# modbus.net
KiCad netlist of a schematic drawn in EAGLE
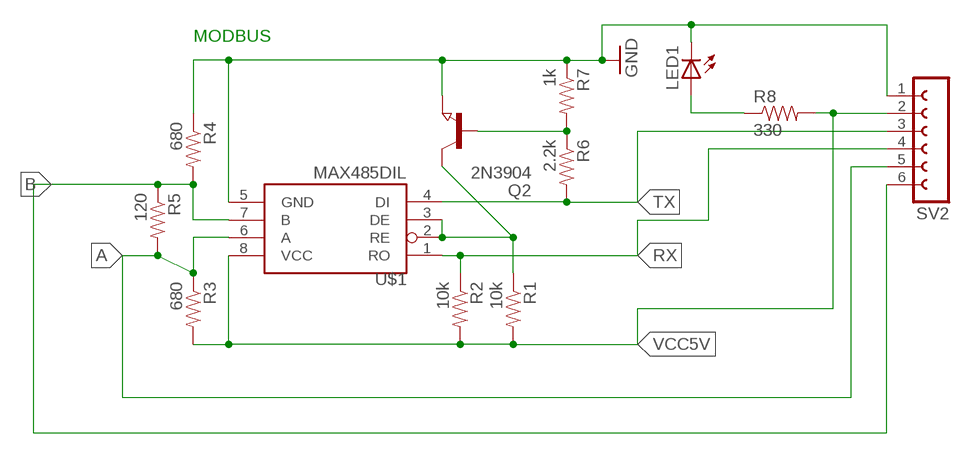
[diagram p0: schematic, sheet 1]

(export (version "E")
  (design (tool "Eeschema 10.0.6"))
  (components
    (comp (ref "LED1")
      (value "LEDCHIP-LED0805")
      (footprint "eagle-import:CHIP-LED0805")
      (libsource (lib "eagle-import") (part "LEDCHIP-LED0805"))
    )
    (comp (ref "Q2")
      (value "2N3904")
      (footprint "eagle-import:SOT23")
      (libsource (lib "eagle-import") (part "NPN-TRANSISTOR_SOT23"))
    )
    (comp (ref "R1")
      (value "10k")
      (footprint "eagle-import:0805")
      (libsource (lib "eagle-import") (part "RESISTOR0805-RES"))
    )
    (comp (ref "R2")
      (value "10k")
      (footprint "eagle-import:0805")
      (libsource (lib "eagle-import") (part "RESISTOR0805-RES"))
    )
    (comp (ref "R3")
      (value "680")
      (footprint "eagle-import:0805")
      (libsource (lib "eagle-import") (part "RESISTOR0805-RES"))
    )
    (comp (ref "R4")
      (value "680")
      (footprint "eagle-import:0805")
      (libsource (lib "eagle-import") (part "RESISTOR0805-RES"))
    )
    (comp (ref "R5")
      (value "120")
      (footprint "eagle-import:0805")
      (libsource (lib "eagle-import") (part "RESISTOR0805-RES"))
    )
    (comp (ref "R6")
      (value "2.2k")
      (footprint "eagle-import:0805")
      (libsource (lib "eagle-import") (part "RESISTOR0805-RES"))
    )
    (comp (ref "R7")
      (value "1k")
      (footprint "eagle-import:0805")
      (libsource (lib "eagle-import") (part "RESISTOR0805-RES"))
    )
    (comp (ref "R8")
      (value "330")
      (footprint "eagle-import:0805")
      (libsource (lib "eagle-import") (part "RESISTOR0805-RES"))
    )
    (comp (ref "SV2")
      (value "FE06-1")
      (footprint "eagle-import:FE06")
      (libsource (lib "eagle-import") (part "FE06-1"))
    )
    (comp (ref "U$1")
      (value "MAX485DIL")
      (footprint "eagle-import:DIL08")
      (libsource (lib "eagle-import") (part "MAX485DIL"))
    )
  )
  (nets
    (net (code "1") (name "A") (class "Default")
      (node (ref "R3") (pin "1") (pinfunction "1_1") (pintype "passive"))
      (node (ref "R5") (pin "2") (pinfunction "2_2") (pintype "passive"))
      (node (ref "SV2") (pin "5") (pinfunction "5_5") (pintype "passive"))
      (node (ref "U$1") (pin "6") (pinfunction "A_6") (pintype "bidirectional"))
    )
    (net (code "2") (name "B") (class "Default")
      (node (ref "R4") (pin "2") (pinfunction "2_2") (pintype "passive"))
      (node (ref "R5") (pin "1") (pinfunction "1_1") (pintype "passive"))
      (node (ref "SV2") (pin "6") (pinfunction "6_6") (pintype "passive"))
      (node (ref "U$1") (pin "7") (pinfunction "B_7") (pintype "bidirectional"))
    )
    (net (code "3") (name "GND") (class "Default")
      (node (ref "LED1") (pin "C") (pinfunction "C_C") (pintype "passive"))
      (node (ref "Q2") (pin "2") (pinfunction "E_2") (pintype "passive"))
      (node (ref "R4") (pin "1") (pinfunction "1_1") (pintype "passive"))
      (node (ref "R7") (pin "1") (pinfunction "1_1") (pintype "passive"))
      (node (ref "SV2") (pin "1") (pinfunction "1_1") (pintype "passive"))
      (node (ref "U$1") (pin "5") (pinfunction "GND_5") (pintype "bidirectional"))
    )
    (net (code "4") (name "Net-(LED1-PadA)") (class "Default")
      (node (ref "LED1") (pin "A") (pinfunction "A_A") (pintype "passive"))
      (node (ref "R8") (pin "1") (pinfunction "1_1") (pintype "passive"))
    )
    (net (code "5") (name "Net-(Q2-B)") (class "Default")
      (node (ref "Q2") (pin "1") (pinfunction "B_1") (pintype "passive"))
      (node (ref "R6") (pin "1") (pinfunction "1_1") (pintype "passive"))
      (node (ref "R7") (pin "2") (pinfunction "2_2") (pintype "passive"))
    )
    (net (code "6") (name "Net-(Q2-C)") (class "Default")
      (node (ref "Q2") (pin "3") (pinfunction "C_3") (pintype "passive"))
      (node (ref "R1") (pin "1") (pinfunction "1_1") (pintype "passive"))
      (node (ref "U$1") (pin "2") (pinfunction "RE_2") (pintype "bidirectional"))
      (node (ref "U$1") (pin "3") (pinfunction "DE_3") (pintype "bidirectional"))
    )
    (net (code "7") (name "RX") (class "Default")
      (node (ref "R2") (pin "1") (pinfunction "1_1") (pintype "passive"))
      (node (ref "SV2") (pin "4") (pinfunction "4_4") (pintype "passive"))
      (node (ref "U$1") (pin "1") (pinfunction "RO_1") (pintype "bidirectional"))
    )
    (net (code "8") (name "TX") (class "Default")
      (node (ref "R6") (pin "2") (pinfunction "2_2") (pintype "passive"))
      (node (ref "SV2") (pin "3") (pinfunction "3_3") (pintype "passive"))
      (node (ref "U$1") (pin "4") (pinfunction "DI_4") (pintype "bidirectional"))
    )
    (net (code "9") (name "VCC5V") (class "Default")
      (node (ref "R1") (pin "2") (pinfunction "2_2") (pintype "passive"))
      (node (ref "R2") (pin "2") (pinfunction "2_2") (pintype "passive"))
      (node (ref "R3") (pin "2") (pinfunction "2_2") (pintype "passive"))
      (node (ref "R8") (pin "2") (pinfunction "2_2") (pintype "passive"))
      (node (ref "SV2") (pin "2") (pinfunction "2_2") (pintype "passive"))
      (node (ref "U$1") (pin "8") (pinfunction "VCC_8") (pintype "bidirectional"))
    )
  )
)
